# EEM_Connectors.net
KiCad netlist of a schematic drawn in Altium Designer
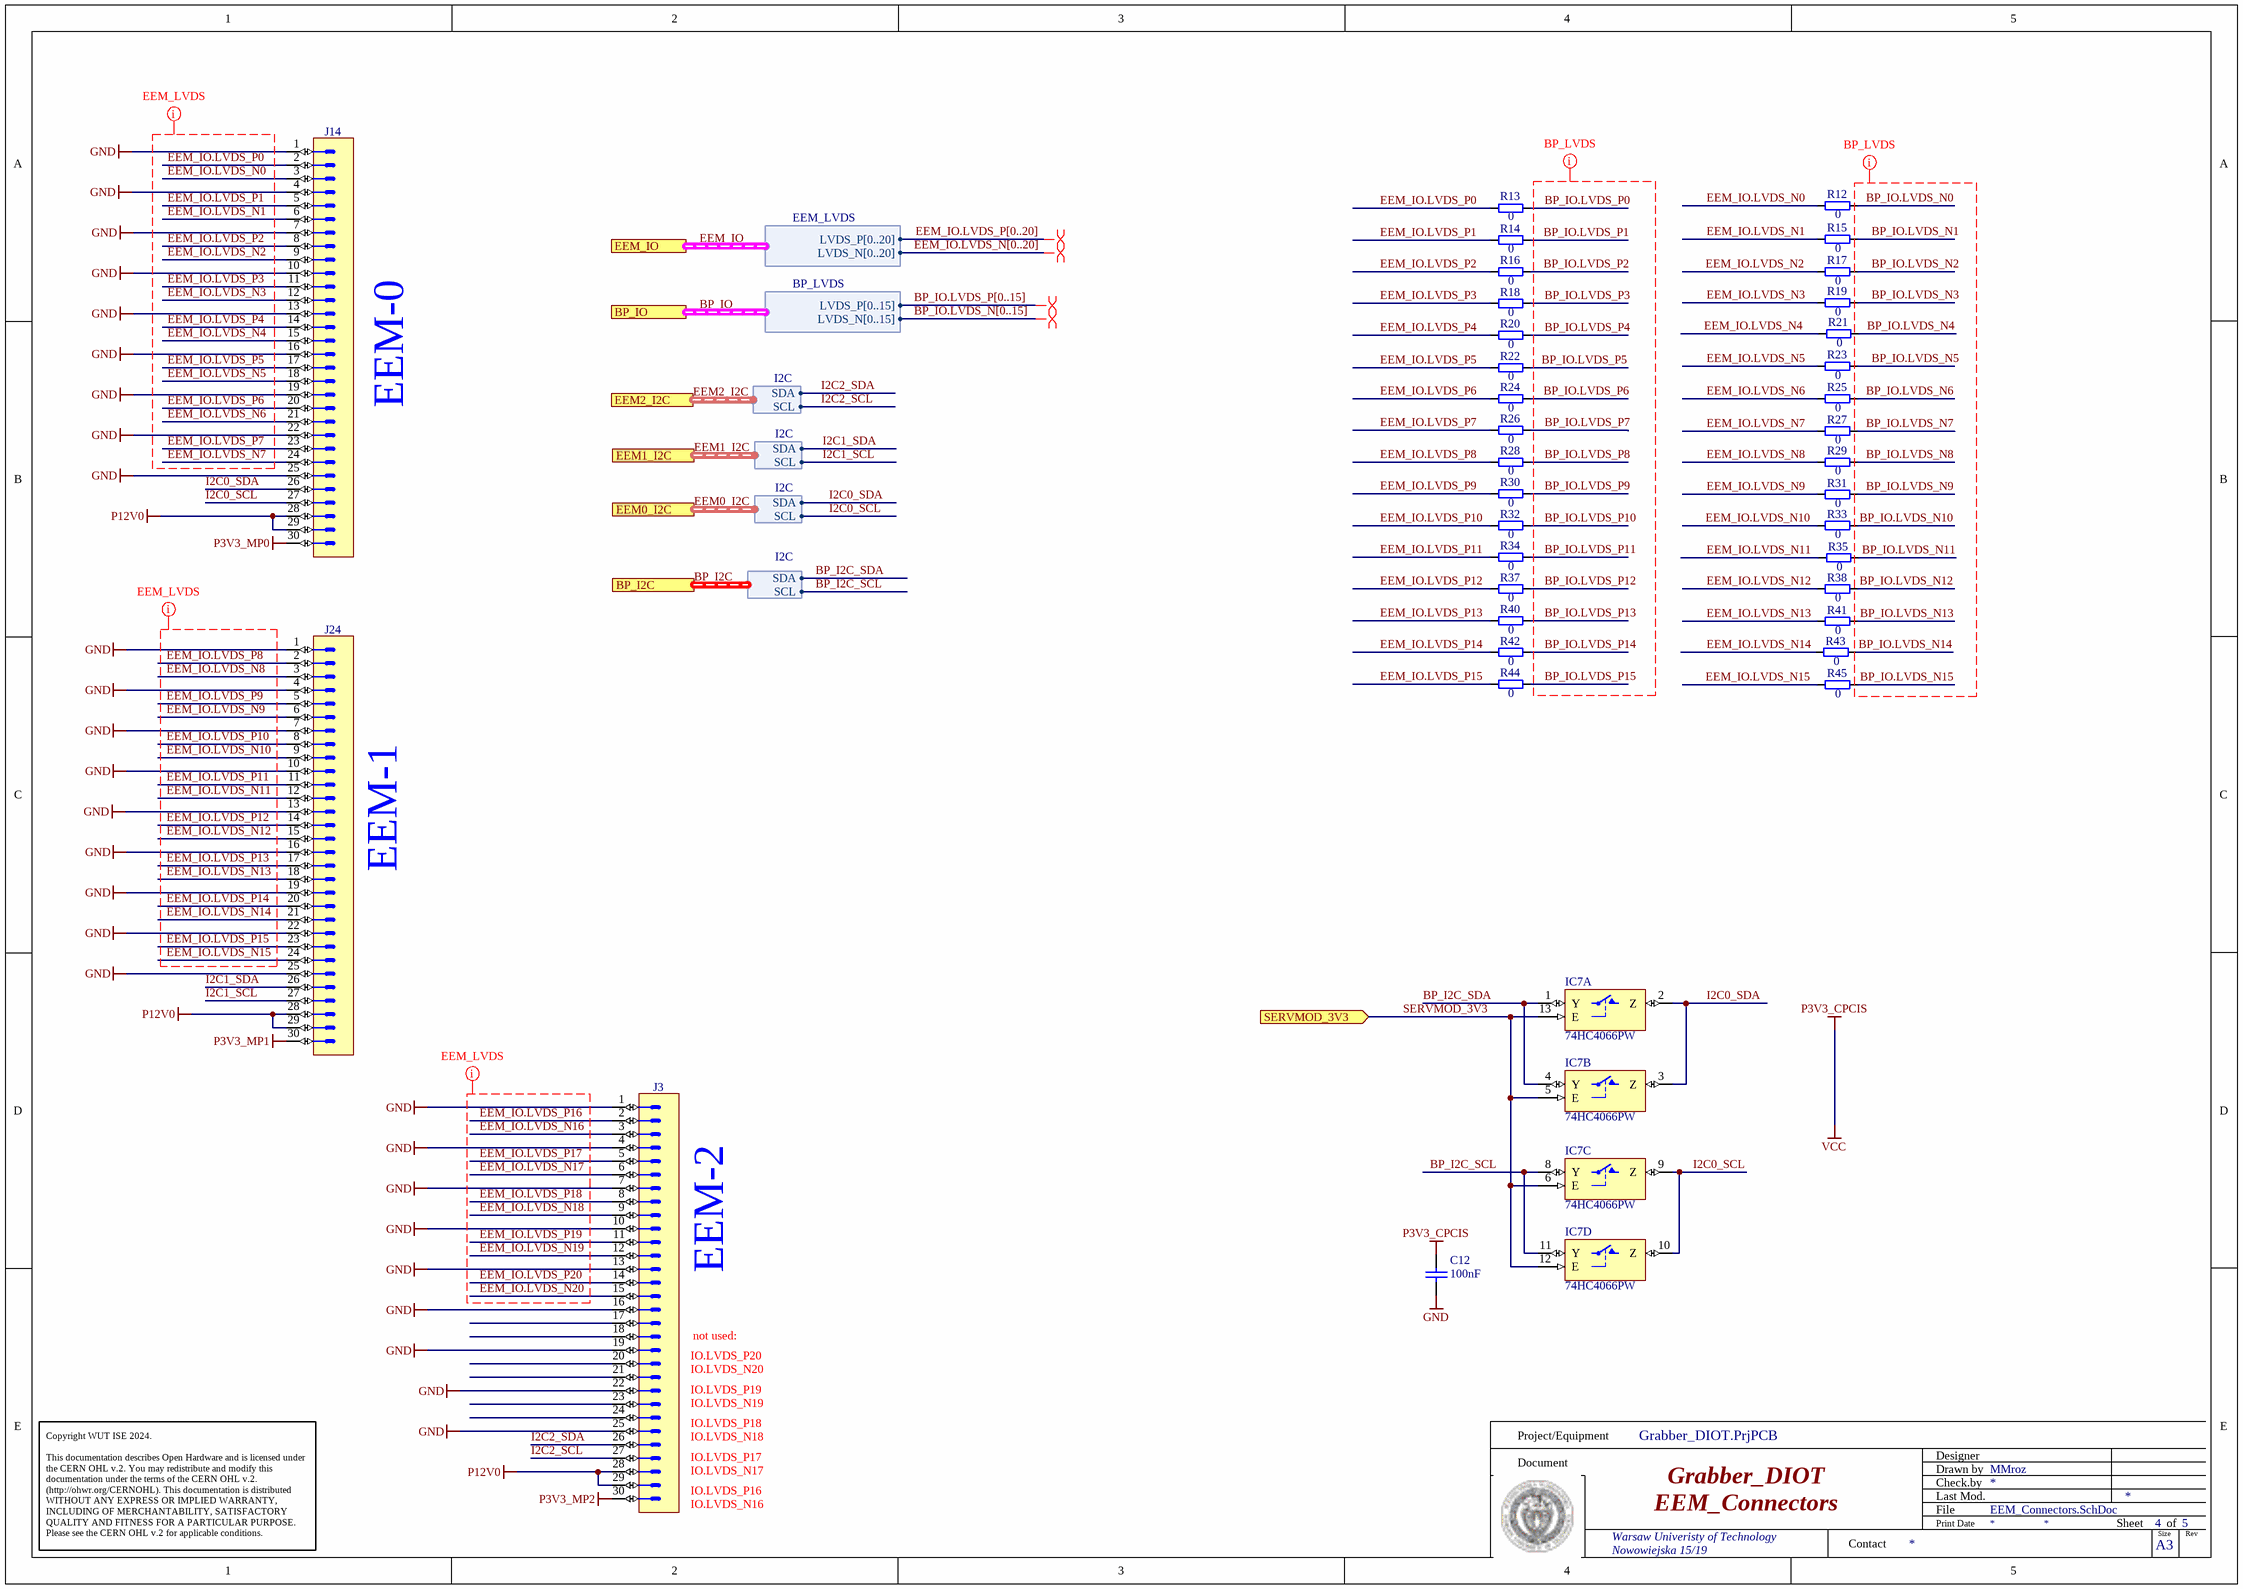
[diagram p0: EEM_Connectors.SchDoc]

(export (version "E")
  (design (tool "Eeschema 10.0.6"))
  (components
    (comp (ref "C12")
      (value "100nF")
      (footprint "CAPC1608X87N")
      (description "Non-polarised capacitor")
      (fields
        (field (name "PART NUMBER") "CC0603_100NF_50V_10%_X7R")
        (field (name "VOLTAGE") "50V")
        (field (name "AUTHOR") "CERN DEM JLC")
      )
      (libsource (lib "Capacitors") (part "Capacitor - non polarized"))
    )
    (comp (ref "IC7")
      (value "74HC4066PW")
      (footprint "SOP65P640X110-14N")
      (fields (field (name "MANUFACTURER") "NXP SEMICONDUCTORS") (field (name "AUTHOR") "CERN DEM JLC"))
      (libsource (lib "ICs And Semiconductors") (part "4066"))
    )
    (comp (ref "J3")
      (value "N2530-6002RB")
      (footprint "3M_N2530-6002RB")
      (description "30 Contacts - Straight .100'' x .100'' Low Profile Four-Wall Header, 2500 Series")
      (fields
        (field (name "PART NUMBER") "3M_N2530-6002RB")
        (field (name "MANUFACTURER") "3M")
        (field (name "AUTHOR") "CERN DEM JLC")
      )
      (libsource (lib "Connectors") (part "Connector 30 Male"))
    )
    (comp (ref "J14")
      (value "N2530-6002RB")
      (footprint "3M_N2530-6002RB")
      (description "30 Contacts - Straight .100'' x .100'' Low Profile Four-Wall Header, 2500 Series")
      (fields
        (field (name "PART NUMBER") "3M_N2530-6002RB")
        (field (name "MANUFACTURER") "3M")
        (field (name "AUTHOR") "CERN DEM JLC")
      )
      (libsource (lib "Connectors") (part "Connector 30 Male"))
    )
    (comp (ref "J24")
      (value "N2530-6002RB")
      (footprint "3M_N2530-6002RB")
      (description "30 Contacts - Straight .100'' x .100'' Low Profile Four-Wall Header, 2500 Series")
      (fields
        (field (name "PART NUMBER") "3M_N2530-6002RB")
        (field (name "MANUFACTURER") "3M")
        (field (name "AUTHOR") "CERN DEM JLC")
      )
      (libsource (lib "Connectors") (part "Connector 30 Male"))
    )
    (comp (ref "R12")
      (value "0")
      (footprint "RESC1005X40N")
      (description "Resistor")
      (fields
        (field (name "PART NUMBER") "R0402_0R_JUMPER")
        (field (name "MANUFACTURER") "GENERIC")
        (field (name "AUTHOR") "CERN DEM JLC")
      )
      (libsource (lib "Resistors") (part "Resistor"))
    )
    (comp (ref "R13")
      (value "0")
      (footprint "RESC1005X40N")
      (description "Resistor")
      (fields
        (field (name "PART NUMBER") "R0402_0R_JUMPER")
        (field (name "MANUFACTURER") "GENERIC")
        (field (name "AUTHOR") "CERN DEM JLC")
      )
      (libsource (lib "Resistors") (part "Resistor"))
    )
    (comp (ref "R14")
      (value "0")
      (footprint "RESC1005X40N")
      (description "Resistor")
      (fields
        (field (name "PART NUMBER") "R0402_0R_JUMPER")
        (field (name "MANUFACTURER") "GENERIC")
        (field (name "AUTHOR") "CERN DEM JLC")
      )
      (libsource (lib "Resistors") (part "Resistor"))
    )
    (comp (ref "R15")
      (value "0")
      (footprint "RESC1005X40N")
      (description "Resistor")
      (fields
        (field (name "PART NUMBER") "R0402_0R_JUMPER")
        (field (name "MANUFACTURER") "GENERIC")
        (field (name "AUTHOR") "CERN DEM JLC")
      )
      (libsource (lib "Resistors") (part "Resistor"))
    )
    (comp (ref "R16")
      (value "0")
      (footprint "RESC1005X40N")
      (description "Resistor")
      (fields
        (field (name "PART NUMBER") "R0402_0R_JUMPER")
        (field (name "MANUFACTURER") "GENERIC")
        (field (name "AUTHOR") "CERN DEM JLC")
      )
      (libsource (lib "Resistors") (part "Resistor"))
    )
    (comp (ref "R17")
      (value "0")
      (footprint "RESC1005X40N")
      (description "Resistor")
      (fields
        (field (name "PART NUMBER") "R0402_0R_JUMPER")
        (field (name "MANUFACTURER") "GENERIC")
        (field (name "AUTHOR") "CERN DEM JLC")
      )
      (libsource (lib "Resistors") (part "Resistor"))
    )
    (comp (ref "R18")
      (value "0")
      (footprint "RESC1005X40N")
      (description "Resistor")
      (fields
        (field (name "PART NUMBER") "R0402_0R_JUMPER")
        (field (name "MANUFACTURER") "GENERIC")
        (field (name "AUTHOR") "CERN DEM JLC")
      )
      (libsource (lib "Resistors") (part "Resistor"))
    )
    (comp (ref "R19")
      (value "0")
      (footprint "RESC1005X40N")
      (description "Resistor")
      (fields
        (field (name "PART NUMBER") "R0402_0R_JUMPER")
        (field (name "MANUFACTURER") "GENERIC")
        (field (name "AUTHOR") "CERN DEM JLC")
      )
      (libsource (lib "Resistors") (part "Resistor"))
    )
    (comp (ref "R20")
      (value "0")
      (footprint "RESC1005X40N")
      (description "Resistor")
      (fields
        (field (name "PART NUMBER") "R0402_0R_JUMPER")
        (field (name "MANUFACTURER") "GENERIC")
        (field (name "AUTHOR") "CERN DEM JLC")
      )
      (libsource (lib "Resistors") (part "Resistor"))
    )
    (comp (ref "R21")
      (value "0")
      (footprint "RESC1005X40N")
      (description "Resistor")
      (fields
        (field (name "PART NUMBER") "R0402_0R_JUMPER")
        (field (name "MANUFACTURER") "GENERIC")
        (field (name "AUTHOR") "CERN DEM JLC")
      )
      (libsource (lib "Resistors") (part "Resistor"))
    )
    (comp (ref "R22")
      (value "0")
      (footprint "RESC1005X40N")
      (description "Resistor")
      (fields
        (field (name "PART NUMBER") "R0402_0R_JUMPER")
        (field (name "MANUFACTURER") "GENERIC")
        (field (name "AUTHOR") "CERN DEM JLC")
      )
      (libsource (lib "Resistors") (part "Resistor"))
    )
    (comp (ref "R23")
      (value "0")
      (footprint "RESC1005X40N")
      (description "Resistor")
      (fields
        (field (name "PART NUMBER") "R0402_0R_JUMPER")
        (field (name "MANUFACTURER") "GENERIC")
        (field (name "AUTHOR") "CERN DEM JLC")
      )
      (libsource (lib "Resistors") (part "Resistor"))
    )
    (comp (ref "R24")
      (value "0")
      (footprint "RESC1005X40N")
      (description "Resistor")
      (fields
        (field (name "PART NUMBER") "R0402_0R_JUMPER")
        (field (name "MANUFACTURER") "GENERIC")
        (field (name "AUTHOR") "CERN DEM JLC")
      )
      (libsource (lib "Resistors") (part "Resistor"))
    )
    (comp (ref "R25")
      (value "0")
      (footprint "RESC1005X40N")
      (description "Resistor")
      (fields
        (field (name "PART NUMBER") "R0402_0R_JUMPER")
        (field (name "MANUFACTURER") "GENERIC")
        (field (name "AUTHOR") "CERN DEM JLC")
      )
      (libsource (lib "Resistors") (part "Resistor"))
    )
    (comp (ref "R26")
      (value "0")
      (footprint "RESC1005X40N")
      (description "Resistor")
      (fields
        (field (name "PART NUMBER") "R0402_0R_JUMPER")
        (field (name "MANUFACTURER") "GENERIC")
        (field (name "AUTHOR") "CERN DEM JLC")
      )
      (libsource (lib "Resistors") (part "Resistor"))
    )
    (comp (ref "R27")
      (value "0")
      (footprint "RESC1005X40N")
      (description "Resistor")
      (fields
        (field (name "PART NUMBER") "R0402_0R_JUMPER")
        (field (name "MANUFACTURER") "GENERIC")
        (field (name "AUTHOR") "CERN DEM JLC")
      )
      (libsource (lib "Resistors") (part "Resistor"))
    )
    (comp (ref "R28")
      (value "0")
      (footprint "RESC1005X40N")
      (description "Resistor")
      (fields
        (field (name "PART NUMBER") "R0402_0R_JUMPER")
        (field (name "MANUFACTURER") "GENERIC")
        (field (name "AUTHOR") "CERN DEM JLC")
      )
      (libsource (lib "Resistors") (part "Resistor"))
    )
    (comp (ref "R29")
      (value "0")
      (footprint "RESC1005X40N")
      (description "Resistor")
      (fields
        (field (name "PART NUMBER") "R0402_0R_JUMPER")
        (field (name "MANUFACTURER") "GENERIC")
        (field (name "AUTHOR") "CERN DEM JLC")
      )
      (libsource (lib "Resistors") (part "Resistor"))
    )
    (comp (ref "R30")
      (value "0")
      (footprint "RESC1005X40N")
      (description "Resistor")
      (fields
        (field (name "PART NUMBER") "R0402_0R_JUMPER")
        (field (name "MANUFACTURER") "GENERIC")
        (field (name "AUTHOR") "CERN DEM JLC")
      )
      (libsource (lib "Resistors") (part "Resistor"))
    )
    (comp (ref "R31")
      (value "0")
      (footprint "RESC1005X40N")
      (description "Resistor")
      (fields
        (field (name "PART NUMBER") "R0402_0R_JUMPER")
        (field (name "MANUFACTURER") "GENERIC")
        (field (name "AUTHOR") "CERN DEM JLC")
      )
      (libsource (lib "Resistors") (part "Resistor"))
    )
    (comp (ref "R32")
      (value "0")
      (footprint "RESC1005X40N")
      (description "Resistor")
      (fields
        (field (name "PART NUMBER") "R0402_0R_JUMPER")
        (field (name "MANUFACTURER") "GENERIC")
        (field (name "AUTHOR") "CERN DEM JLC")
      )
      (libsource (lib "Resistors") (part "Resistor"))
    )
    (comp (ref "R33")
      (value "0")
      (footprint "RESC1005X40N")
      (description "Resistor")
      (fields
        (field (name "PART NUMBER") "R0402_0R_JUMPER")
        (field (name "MANUFACTURER") "GENERIC")
        (field (name "AUTHOR") "CERN DEM JLC")
      )
      (libsource (lib "Resistors") (part "Resistor"))
    )
    (comp (ref "R34")
      (value "0")
      (footprint "RESC1005X40N")
      (description "Resistor")
      (fields
        (field (name "PART NUMBER") "R0402_0R_JUMPER")
        (field (name "MANUFACTURER") "GENERIC")
        (field (name "AUTHOR") "CERN DEM JLC")
      )
      (libsource (lib "Resistors") (part "Resistor"))
    )
    (comp (ref "R35")
      (value "0")
      (footprint "RESC1005X40N")
      (description "Resistor")
      (fields
        (field (name "PART NUMBER") "R0402_0R_JUMPER")
        (field (name "MANUFACTURER") "GENERIC")
        (field (name "AUTHOR") "CERN DEM JLC")
      )
      (libsource (lib "Resistors") (part "Resistor"))
    )
    (comp (ref "R37")
      (value "0")
      (footprint "RESC1005X40N")
      (description "Resistor")
      (fields
        (field (name "PART NUMBER") "R0402_0R_JUMPER")
        (field (name "MANUFACTURER") "GENERIC")
        (field (name "AUTHOR") "CERN DEM JLC")
      )
      (libsource (lib "Resistors") (part "Resistor"))
    )
    (comp (ref "R38")
      (value "0")
      (footprint "RESC1005X40N")
      (description "Resistor")
      (fields
        (field (name "PART NUMBER") "R0402_0R_JUMPER")
        (field (name "MANUFACTURER") "GENERIC")
        (field (name "AUTHOR") "CERN DEM JLC")
      )
      (libsource (lib "Resistors") (part "Resistor"))
    )
    (comp (ref "R40")
      (value "0")
      (footprint "RESC1005X40N")
      (description "Resistor")
      (fields
        (field (name "PART NUMBER") "R0402_0R_JUMPER")
        (field (name "MANUFACTURER") "GENERIC")
        (field (name "AUTHOR") "CERN DEM JLC")
      )
      (libsource (lib "Resistors") (part "Resistor"))
    )
    (comp (ref "R41")
      (value "0")
      (footprint "RESC1005X40N")
      (description "Resistor")
      (fields
        (field (name "PART NUMBER") "R0402_0R_JUMPER")
        (field (name "MANUFACTURER") "GENERIC")
        (field (name "AUTHOR") "CERN DEM JLC")
      )
      (libsource (lib "Resistors") (part "Resistor"))
    )
    (comp (ref "R42")
      (value "0")
      (footprint "RESC1005X40N")
      (description "Resistor")
      (fields
        (field (name "PART NUMBER") "R0402_0R_JUMPER")
        (field (name "MANUFACTURER") "GENERIC")
        (field (name "AUTHOR") "CERN DEM JLC")
      )
      (libsource (lib "Resistors") (part "Resistor"))
    )
    (comp (ref "R43")
      (value "0")
      (footprint "RESC1005X40N")
      (description "Resistor")
      (fields
        (field (name "PART NUMBER") "R0402_0R_JUMPER")
        (field (name "MANUFACTURER") "GENERIC")
        (field (name "AUTHOR") "CERN DEM JLC")
      )
      (libsource (lib "Resistors") (part "Resistor"))
    )
    (comp (ref "R44")
      (value "0")
      (footprint "RESC1005X40N")
      (description "Resistor")
      (fields
        (field (name "PART NUMBER") "R0402_0R_JUMPER")
        (field (name "MANUFACTURER") "GENERIC")
        (field (name "AUTHOR") "CERN DEM JLC")
      )
      (libsource (lib "Resistors") (part "Resistor"))
    )
    (comp (ref "R45")
      (value "0")
      (footprint "RESC1005X40N")
      (description "Resistor")
      (fields
        (field (name "PART NUMBER") "R0402_0R_JUMPER")
        (field (name "MANUFACTURER") "GENERIC")
        (field (name "AUTHOR") "CERN DEM JLC")
      )
      (libsource (lib "Resistors") (part "Resistor"))
    )
  )
  (nets
    (net (code "7") (name "/BP_I2C_SCL") (class "Default")
      (node (ref "IC7") (pin "11") (pinfunction "Y_11") (pintype "bidirectional"))
      (node (ref "IC7") (pin "8") (pinfunction "Y_8") (pintype "bidirectional"))
    )
    (net (code "8") (name "/BP_I2C_SDA") (class "Default")
      (node (ref "IC7") (pin "1") (pinfunction "Y_1") (pintype "bidirectional"))
      (node (ref "IC7") (pin "4") (pinfunction "Y_4") (pintype "bidirectional"))
    )
    (net (code "10") (name "/BP_IO.LVDS_N0") (class "Default")
      (node (ref "R12") (pin "2") (pinfunction "2_2") (pintype "passive"))
    )
    (net (code "11") (name "/BP_IO.LVDS_N1") (class "Default")
      (node (ref "R15") (pin "2") (pinfunction "2_2") (pintype "passive"))
    )
    (net (code "12") (name "/BP_IO.LVDS_N2") (class "Default")
      (node (ref "R17") (pin "2") (pinfunction "2_2") (pintype "passive"))
    )
    (net (code "13") (name "/BP_IO.LVDS_N3") (class "Default")
      (node (ref "R19") (pin "2") (pinfunction "2_2") (pintype "passive"))
    )
    (net (code "14") (name "/BP_IO.LVDS_N4") (class "Default")
      (node (ref "R21") (pin "2") (pinfunction "2_2") (pintype "passive"))
    )
    (net (code "15") (name "/BP_IO.LVDS_N5") (class "Default")
      (node (ref "R23") (pin "2") (pinfunction "2_2") (pintype "passive"))
    )
    (net (code "16") (name "/BP_IO.LVDS_N6") (class "Default")
      (node (ref "R25") (pin "2") (pinfunction "2_2") (pintype "passive"))
    )
    (net (code "17") (name "/BP_IO.LVDS_N7") (class "Default")
      (node (ref "R27") (pin "2") (pinfunction "2_2") (pintype "passive"))
    )
    (net (code "18") (name "/BP_IO.LVDS_N8") (class "Default")
      (node (ref "R29") (pin "2") (pinfunction "2_2") (pintype "passive"))
    )
    (net (code "19") (name "/BP_IO.LVDS_N9") (class "Default")
      (node (ref "R31") (pin "2") (pinfunction "2_2") (pintype "passive"))
    )
    (net (code "20") (name "/BP_IO.LVDS_N10") (class "Default")
      (node (ref "R33") (pin "2") (pinfunction "2_2") (pintype "passive"))
    )
    (net (code "21") (name "/BP_IO.LVDS_N11") (class "Default")
      (node (ref "R35") (pin "2") (pinfunction "2_2") (pintype "passive"))
    )
    (net (code "22") (name "/BP_IO.LVDS_N12") (class "Default")
      (node (ref "R38") (pin "2") (pinfunction "2_2") (pintype "passive"))
    )
    (net (code "23") (name "/BP_IO.LVDS_N13") (class "Default")
      (node (ref "R41") (pin "2") (pinfunction "2_2") (pintype "passive"))
    )
    (net (code "24") (name "/BP_IO.LVDS_N14") (class "Default")
      (node (ref "R43") (pin "2") (pinfunction "2_2") (pintype "passive"))
    )
    (net (code "25") (name "/BP_IO.LVDS_N15") (class "Default")
      (node (ref "R45") (pin "2") (pinfunction "2_2") (pintype "passive"))
    )
    (net (code "27") (name "/BP_IO.LVDS_P0") (class "Default")
      (node (ref "R13") (pin "2") (pinfunction "2_2") (pintype "passive"))
    )
    (net (code "28") (name "/BP_IO.LVDS_P1") (class "Default")
      (node (ref "R14") (pin "2") (pinfunction "2_2") (pintype "passive"))
    )
    (net (code "29") (name "/BP_IO.LVDS_P2") (class "Default")
      (node (ref "R16") (pin "2") (pinfunction "2_2") (pintype "passive"))
    )
    (net (code "30") (name "/BP_IO.LVDS_P3") (class "Default")
      (node (ref "R18") (pin "2") (pinfunction "2_2") (pintype "passive"))
    )
    (net (code "31") (name "/BP_IO.LVDS_P4") (class "Default")
      (node (ref "R20") (pin "2") (pinfunction "2_2") (pintype "passive"))
    )
    (net (code "32") (name "/BP_IO.LVDS_P5") (class "Default")
      (node (ref "R22") (pin "2") (pinfunction "2_2") (pintype "passive"))
    )
    (net (code "33") (name "/BP_IO.LVDS_P6") (class "Default")
      (node (ref "R24") (pin "2") (pinfunction "2_2") (pintype "passive"))
    )
    (net (code "34") (name "/BP_IO.LVDS_P7") (class "Default")
      (node (ref "R26") (pin "2") (pinfunction "2_2") (pintype "passive"))
    )
    (net (code "35") (name "/BP_IO.LVDS_P8") (class "Default")
      (node (ref "R28") (pin "2") (pinfunction "2_2") (pintype "passive"))
    )
    (net (code "36") (name "/BP_IO.LVDS_P9") (class "Default")
      (node (ref "R30") (pin "2") (pinfunction "2_2") (pintype "passive"))
    )
    (net (code "37") (name "/BP_IO.LVDS_P10") (class "Default")
      (node (ref "R32") (pin "2") (pinfunction "2_2") (pintype "passive"))
    )
    (net (code "38") (name "/BP_IO.LVDS_P11") (class "Default")
      (node (ref "R34") (pin "2") (pinfunction "2_2") (pintype "passive"))
    )
    (net (code "39") (name "/BP_IO.LVDS_P12") (class "Default")
      (node (ref "R37") (pin "2") (pinfunction "2_2") (pintype "passive"))
    )
    (net (code "40") (name "/BP_IO.LVDS_P13") (class "Default")
      (node (ref "R40") (pin "2") (pinfunction "2_2") (pintype "passive"))
    )
    (net (code "41") (name "/BP_IO.LVDS_P14") (class "Default")
      (node (ref "R42") (pin "2") (pinfunction "2_2") (pintype "passive"))
    )
    (net (code "42") (name "/BP_IO.LVDS_P15") (class "Default")
      (node (ref "R44") (pin "2") (pinfunction "2_2") (pintype "passive"))
    )
    (net (code "48") (name "/EEM_IO.LVDS_N0") (class "Default")
      (node (ref "J14") (pin "3") (pinfunction "3_3") (pintype "bidirectional"))
      (node (ref "R12") (pin "1") (pinfunction "1_1") (pintype "passive"))
    )
    (net (code "49") (name "/EEM_IO.LVDS_N1") (class "Default")
      (node (ref "J14") (pin "6") (pinfunction "6_6") (pintype "bidirectional"))
      (node (ref "R15") (pin "1") (pinfunction "1_1") (pintype "passive"))
    )
    (net (code "50") (name "/EEM_IO.LVDS_N2") (class "Default")
      (node (ref "J14") (pin "9") (pinfunction "9_9") (pintype "bidirectional"))
      (node (ref "R17") (pin "1") (pinfunction "1_1") (pintype "passive"))
    )
    (net (code "51") (name "/EEM_IO.LVDS_N3") (class "Default")
      (node (ref "J14") (pin "12") (pinfunction "12_12") (pintype "bidirectional"))
      (node (ref "R19") (pin "1") (pinfunction "1_1") (pintype "passive"))
    )
    (net (code "52") (name "/EEM_IO.LVDS_N4") (class "Default")
      (node (ref "J14") (pin "15") (pinfunction "15_15") (pintype "bidirectional"))
      (node (ref "R21") (pin "1") (pinfunction "1_1") (pintype "passive"))
    )
    (net (code "53") (name "/EEM_IO.LVDS_N5") (class "Default")
      (node (ref "J14") (pin "18") (pinfunction "18_18") (pintype "bidirectional"))
      (node (ref "R23") (pin "1") (pinfunction "1_1") (pintype "passive"))
    )
    (net (code "54") (name "/EEM_IO.LVDS_N6") (class "Default")
      (node (ref "J14") (pin "21") (pinfunction "21_21") (pintype "bidirectional"))
      (node (ref "R25") (pin "1") (pinfunction "1_1") (pintype "passive"))
    )
    (net (code "55") (name "/EEM_IO.LVDS_N7") (class "Default")
      (node (ref "J14") (pin "24") (pinfunction "24_24") (pintype "bidirectional"))
      (node (ref "R27") (pin "1") (pinfunction "1_1") (pintype "passive"))
    )
    (net (code "56") (name "/EEM_IO.LVDS_N8") (class "Default")
      (node (ref "J24") (pin "3") (pinfunction "3_3") (pintype "bidirectional"))
      (node (ref "R29") (pin "1") (pinfunction "1_1") (pintype "passive"))
    )
    (net (code "57") (name "/EEM_IO.LVDS_N9") (class "Default")
      (node (ref "J24") (pin "6") (pinfunction "6_6") (pintype "bidirectional"))
      (node (ref "R31") (pin "1") (pinfunction "1_1") (pintype "passive"))
    )
    (net (code "58") (name "/EEM_IO.LVDS_N10") (class "Default")
      (node (ref "J24") (pin "9") (pinfunction "9_9") (pintype "bidirectional"))
      (node (ref "R33") (pin "1") (pinfunction "1_1") (pintype "passive"))
    )
    (net (code "59") (name "/EEM_IO.LVDS_N11") (class "Default")
      (node (ref "J24") (pin "12") (pinfunction "12_12") (pintype "bidirectional"))
      (node (ref "R35") (pin "1") (pinfunction "1_1") (pintype "passive"))
    )
    (net (code "60") (name "/EEM_IO.LVDS_N12") (class "Default")
      (node (ref "J24") (pin "15") (pinfunction "15_15") (pintype "bidirectional"))
      (node (ref "R38") (pin "1") (pinfunction "1_1") (pintype "passive"))
    )
    (net (code "61") (name "/EEM_IO.LVDS_N13") (class "Default")
      (node (ref "J24") (pin "18") (pinfunction "18_18") (pintype "bidirectional"))
      (node (ref "R41") (pin "1") (pinfunction "1_1") (pintype "passive"))
    )
    (net (code "62") (name "/EEM_IO.LVDS_N14") (class "Default")
      (node (ref "J24") (pin "21") (pinfunction "21_21") (pintype "bidirectional"))
      (node (ref "R43") (pin "1") (pinfunction "1_1") (pintype "passive"))
    )
    (net (code "63") (name "/EEM_IO.LVDS_N15") (class "Default")
      (node (ref "J24") (pin "24") (pinfunction "24_24") (pintype "bidirectional"))
      (node (ref "R45") (pin "1") (pinfunction "1_1") (pintype "passive"))
    )
    (net (code "64") (name "/EEM_IO.LVDS_N16") (class "Default")
      (node (ref "J3") (pin "3") (pinfunction "3_3") (pintype "bidirectional"))
    )
    (net (code "65") (name "/EEM_IO.LVDS_N17") (class "Default")
      (node (ref "J3") (pin "6") (pinfunction "6_6") (pintype "bidirectional"))
    )
    (net (code "66") (name "/EEM_IO.LVDS_N18") (class "Default")
      (node (ref "J3") (pin "9") (pinfunction "9_9") (pintype "bidirectional"))
    )
    (net (code "67") (name "/EEM_IO.LVDS_N19") (class "Default")
      (node (ref "J3") (pin "12") (pinfunction "12_12") (pintype "bidirectional"))
    )
    (net (code "68") (name "/EEM_IO.LVDS_N20") (class "Default")
      (node (ref "J3") (pin "15") (pinfunction "15_15") (pintype "bidirectional"))
    )
    (net (code "70") (name "/EEM_IO.LVDS_P0") (class "Default")
      (node (ref "J14") (pin "2") (pinfunction "2_2") (pintype "bidirectional"))
      (node (ref "R13") (pin "1") (pinfunction "1_1") (pintype "passive"))
    )
    (net (code "71") (name "/EEM_IO.LVDS_P1") (class "Default")
      (node (ref "J14") (pin "5") (pinfunction "5_5") (pintype "bidirectional"))
      (node (ref "R14") (pin "1") (pinfunction "1_1") (pintype "passive"))
    )
    (net (code "72") (name "/EEM_IO.LVDS_P2") (class "Default")
      (node (ref "J14") (pin "8") (pinfunction "8_8") (pintype "bidirectional"))
      (node (ref "R16") (pin "1") (pinfunction "1_1") (pintype "passive"))
    )
    (net (code "73") (name "/EEM_IO.LVDS_P3") (class "Default")
      (node (ref "J14") (pin "11") (pinfunction "11_11") (pintype "bidirectional"))
      (node (ref "R18") (pin "1") (pinfunction "1_1") (pintype "passive"))
    )
    (net (code "74") (name "/EEM_IO.LVDS_P4") (class "Default")
      (node (ref "J14") (pin "14") (pinfunction "14_14") (pintype "bidirectional"))
      (node (ref "R20") (pin "1") (pinfunction "1_1") (pintype "passive"))
    )
    (net (code "75") (name "/EEM_IO.LVDS_P5") (class "Default")
      (node (ref "J14") (pin "17") (pinfunction "17_17") (pintype "bidirectional"))
      (node (ref "R22") (pin "1") (pinfunction "1_1") (pintype "passive"))
    )
    (net (code "76") (name "/EEM_IO.LVDS_P6") (class "Default")
      (node (ref "J14") (pin "20") (pinfunction "20_20") (pintype "bidirectional"))
      (node (ref "R24") (pin "1") (pinfunction "1_1") (pintype "passive"))
    )
    (net (code "77") (name "/EEM_IO.LVDS_P7") (class "Default")
      (node (ref "J14") (pin "23") (pinfunction "23_23") (pintype "bidirectional"))
      (node (ref "R26") (pin "1") (pinfunction "1_1") (pintype "passive"))
    )
    (net (code "78") (name "/EEM_IO.LVDS_P8") (class "Default")
      (node (ref "J24") (pin "2") (pinfunction "2_2") (pintype "bidirectional"))
      (node (ref "R28") (pin "1") (pinfunction "1_1") (pintype "passive"))
    )
    (net (code "79") (name "/EEM_IO.LVDS_P9") (class "Default")
      (node (ref "J24") (pin "5") (pinfunction "5_5") (pintype "bidirectional"))
      (node (ref "R30") (pin "1") (pinfunction "1_1") (pintype "passive"))
    )
    (net (code "80") (name "/EEM_IO.LVDS_P10") (class "Default")
      (node (ref "J24") (pin "8") (pinfunction "8_8") (pintype "bidirectional"))
      (node (ref "R32") (pin "1") (pinfunction "1_1") (pintype "passive"))
    )
    (net (code "81") (name "/EEM_IO.LVDS_P11") (class "Default")
      (node (ref "J24") (pin "11") (pinfunction "11_11") (pintype "bidirectional"))
      (node (ref "R34") (pin "1") (pinfunction "1_1") (pintype "passive"))
    )
    (net (code "82") (name "/EEM_IO.LVDS_P12") (class "Default")
      (node (ref "J24") (pin "14") (pinfunction "14_14") (pintype "bidirectional"))
      (node (ref "R37") (pin "1") (pinfunction "1_1") (pintype "passive"))
    )
    (net (code "83") (name "/EEM_IO.LVDS_P13") (class "Default")
      (node (ref "J24") (pin "17") (pinfunction "17_17") (pintype "bidirectional"))
      (node (ref "R40") (pin "1") (pinfunction "1_1") (pintype "passive"))
    )
    (net (code "84") (name "/EEM_IO.LVDS_P14") (class "Default")
      (node (ref "J24") (pin "20") (pinfunction "20_20") (pintype "bidirectional"))
      (node (ref "R42") (pin "1") (pinfunction "1_1") (pintype "passive"))
    )
    (net (code "85") (name "/EEM_IO.LVDS_P15") (class "Default")
      (node (ref "J24") (pin "23") (pinfunction "23_23") (pintype "bidirectional"))
      (node (ref "R44") (pin "1") (pinfunction "1_1") (pintype "passive"))
    )
    (net (code "86") (name "/EEM_IO.LVDS_P16") (class "Default")
      (node (ref "J3") (pin "2") (pinfunction "2_2") (pintype "bidirectional"))
    )
    (net (code "87") (name "/EEM_IO.LVDS_P17") (class "Default")
      (node (ref "J3") (pin "5") (pinfunction "5_5") (pintype "bidirectional"))
    )
    (net (code "88") (name "/EEM_IO.LVDS_P18") (class "Default")
      (node (ref "J3") (pin "8") (pinfunction "8_8") (pintype "bidirectional"))
    )
    (net (code "89") (name "/EEM_IO.LVDS_P19") (class "Default")
      (node (ref "J3") (pin "11") (pinfunction "11_11") (pintype "bidirectional"))
    )
    (net (code "90") (name "/EEM_IO.LVDS_P20") (class "Default")
      (node (ref "J3") (pin "14") (pinfunction "14_14") (pintype "bidirectional"))
    )
    (net (code "91") (name "/I2C0_SCL") (class "Default")
      (node (ref "IC7") (pin "10") (pinfunction "Z_10") (pintype "bidirectional"))
      (node (ref "IC7") (pin "9") (pinfunction "Z_9") (pintype "bidirectional"))
      (node (ref "J14") (pin "27") (pinfunction "27_27") (pintype "bidirectional"))
    )
    (net (code "92") (name "/I2C0_SDA") (class "Default")
      (node (ref "IC7") (pin "2") (pinfunction "Z_2") (pintype "bidirectional"))
      (node (ref "IC7") (pin "3") (pinfunction "Z_3") (pintype "bidirectional"))
      (node (ref "J14") (pin "26") (pinfunction "26_26") (pintype "bidirectional"))
    )
    (net (code "93") (name "/I2C1_SCL") (class "Default")
      (node (ref "J24") (pin "27") (pinfunction "27_27") (pintype "bidirectional"))
    )
    (net (code "94") (name "/I2C1_SDA") (class "Default")
      (node (ref "J24") (pin "26") (pinfunction "26_26") (pintype "bidirectional"))
    )
    (net (code "95") (name "/I2C2_SCL") (class "Default")
      (node (ref "J3") (pin "27") (pinfunction "27_27") (pintype "bidirectional"))
    )
    (net (code "96") (name "/I2C2_SDA") (class "Default")
      (node (ref "J3") (pin "26") (pinfunction "26_26") (pintype "bidirectional"))
    )
    (net (code "97") (name "/SERVMOD_3V3") (class "Default")
      (node (ref "IC7") (pin "12") (pinfunction "E_12") (pintype "input"))
      (node (ref "IC7") (pin "13") (pinfunction "E_13") (pintype "input"))
      (node (ref "IC7") (pin "5") (pinfunction "E_5") (pintype "input"))
      (node (ref "IC7") (pin "6") (pinfunction "E_6") (pintype "input"))
    )
    (net (code "100") (name "GND") (class "Default")
      (node (ref "C12") (pin "1") (pinfunction "1_1") (pintype "passive"))
      (node (ref "IC7") (pin "7") (pinfunction "GND_7") (pintype "power_in"))
      (node (ref "J14") (pin "1") (pinfunction "1_1") (pintype "bidirectional"))
      (node (ref "J14") (pin "10") (pinfunction "10_10") (pintype "bidirectional"))
      (node (ref "J14") (pin "13") (pinfunction "13_13") (pintype "bidirectional"))
      (node (ref "J14") (pin "16") (pinfunction "16_16") (pintype "bidirectional"))
      (node (ref "J14") (pin "19") (pinfunction "19_19") (pintype "bidirectional"))
      (node (ref "J14") (pin "22") (pinfunction "22_22") (pintype "bidirectional"))
      (node (ref "J14") (pin "25") (pinfunction "25_25") (pintype "bidirectional"))
      (node (ref "J14") (pin "4") (pinfunction "4_4") (pintype "bidirectional"))
      (node (ref "J14") (pin "7") (pinfunction "7_7") (pintype "bidirectional"))
      (node (ref "J24") (pin "1") (pinfunction "1_1") (pintype "bidirectional"))
      (node (ref "J24") (pin "10") (pinfunction "10_10") (pintype "bidirectional"))
      (node (ref "J24") (pin "13") (pinfunction "13_13") (pintype "bidirectional"))
      (node (ref "J24") (pin "16") (pinfunction "16_16") (pintype "bidirectional"))
      (node (ref "J24") (pin "19") (pinfunction "19_19") (pintype "bidirectional"))
      (node (ref "J24") (pin "22") (pinfunction "22_22") (pintype "bidirectional"))
      (node (ref "J24") (pin "25") (pinfunction "25_25") (pintype "bidirectional"))
      (node (ref "J24") (pin "4") (pinfunction "4_4") (pintype "bidirectional"))
      (node (ref "J24") (pin "7") (pinfunction "7_7") (pintype "bidirectional"))
      (node (ref "J3") (pin "1") (pinfunction "1_1") (pintype "bidirectional"))
      (node (ref "J3") (pin "10") (pinfunction "10_10") (pintype "bidirectional"))
      (node (ref "J3") (pin "13") (pinfunction "13_13") (pintype "bidirectional"))
      (node (ref "J3") (pin "16") (pinfunction "16_16") (pintype "bidirectional"))
      (node (ref "J3") (pin "19") (pinfunction "19_19") (pintype "bidirectional"))
      (node (ref "J3") (pin "22") (pinfunction "22_22") (pintype "bidirectional"))
      (node (ref "J3") (pin "25") (pinfunction "25_25") (pintype "bidirectional"))
      (node (ref "J3") (pin "4") (pinfunction "4_4") (pintype "bidirectional"))
      (node (ref "J3") (pin "7") (pinfunction "7_7") (pintype "bidirectional"))
    )
    (net (code "101") (name "P3V3_CPCIS") (class "Default")
      (node (ref "C12") (pin "2") (pinfunction "2_2") (pintype "passive"))
      (node (ref "IC7") (pin "14") (pinfunction "VCC_14") (pintype "power_in"))
    )
    (net (code "102") (name "P3V3_MP0") (class "Default")
      (node (ref "J14") (pin "30") (pinfunction "30_30") (pintype "bidirectional"))
    )
    (net (code "103") (name "P3V3_MP1") (class "Default")
      (node (ref "J24") (pin "30") (pinfunction "30_30") (pintype "bidirectional"))
    )
    (net (code "104") (name "P3V3_MP2") (class "Default")
      (node (ref "J3") (pin "30") (pinfunction "30_30") (pintype "bidirectional"))
    )
    (net (code "105") (name "P12V0") (class "Default")
      (node (ref "J14") (pin "28") (pinfunction "28_28") (pintype "bidirectional"))
      (node (ref "J14") (pin "29") (pinfunction "29_29") (pintype "bidirectional"))
      (node (ref "J24") (pin "28") (pinfunction "28_28") (pintype "bidirectional"))
      (node (ref "J24") (pin "29") (pinfunction "29_29") (pintype "bidirectional"))
      (node (ref "J3") (pin "28") (pinfunction "28_28") (pintype "bidirectional"))
      (node (ref "J3") (pin "29") (pinfunction "29_29") (pintype "bidirectional"))
    )
    (net (code "106") (name "unconnected-(J3-Pad17)") (class "Default")
      (node (ref "J3") (pin "17") (pinfunction "17_17") (pintype "bidirectional"))
    )
    (net (code "107") (name "unconnected-(J3-Pad18)") (class "Default")
      (node (ref "J3") (pin "18") (pinfunction "18_18") (pintype "bidirectional"))
    )
    (net (code "108") (name "unconnected-(J3-Pad20)") (class "Default")
      (node (ref "J3") (pin "20") (pinfunction "20_20") (pintype "bidirectional"))
    )
    (net (code "109") (name "unconnected-(J3-Pad21)") (class "Default")
      (node (ref "J3") (pin "21") (pinfunction "21_21") (pintype "bidirectional"))
    )
    (net (code "110") (name "unconnected-(J3-Pad23)") (class "Default")
      (node (ref "J3") (pin "23") (pinfunction "23_23") (pintype "bidirectional"))
    )
    (net (code "111") (name "unconnected-(J3-Pad24)") (class "Default")
      (node (ref "J3") (pin "24") (pinfunction "24_24") (pintype "bidirectional"))
    )
  )
)
